# Rails.net
KiCad netlist of a schematic drawn in Altium Designer
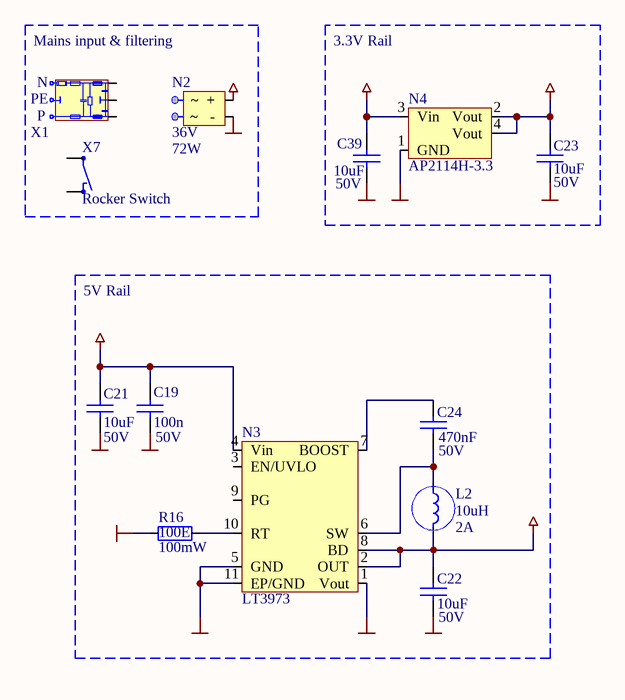
[diagram p0: Rails.SCHDOC]

(export (version "E")
  (design (tool "Eeschema 10.0.6"))
  (components
    (comp (ref "C19")
      (value "C_SMD_CER_100N_50V_10%_X7R_0603")
      (footprint "SMD_0603")
      (description "SMD Capacitor")
      (fields (field (name "ALTIUM_VALUE") "100n") (field (name "VALUE2") "50V"))
      (libsource (lib "C-Capacitor") (part "C_SMD_CER_100N_50V_10%_X7R_0603"))
    )
    (comp (ref "C21")
      (value "C_SMD_CER_10U_50V_10%_X7R_1210")
      (footprint "SMD_1210")
      (description "SMD Ceramic capacitor")
      (fields (field (name "ALTIUM_VALUE") "10uF") (field (name "VALUE2") "50V"))
      (libsource (lib "AM") (part "C_SMD_CER_10U_50V_10%_X7R_1210"))
    )
    (comp (ref "C22")
      (value "C_SMD_CER_10U_50V_10%_X7R_1210")
      (footprint "SMD_1210")
      (description "SMD Ceramic capacitor")
      (fields (field (name "ALTIUM_VALUE") "10uF") (field (name "VALUE2") "50V"))
      (libsource (lib "AM") (part "C_SMD_CER_10U_50V_10%_X7R_1210"))
    )
    (comp (ref "C23")
      (value "C_SMD_CER_10U_50V_10%_X7R_1210")
      (footprint "SMD_1210")
      (description "SMD Ceramic capacitor")
      (fields (field (name "ALTIUM_VALUE") "10uF") (field (name "VALUE2") "50V"))
      (libsource (lib "AM") (part "C_SMD_CER_10U_50V_10%_X7R_1210"))
    )
    (comp (ref "C24")
      (value "C_SMD_CER_470N_50V_10%_X7R_0603")
      (footprint "SMD_0603")
      (fields (field (name "ALTIUM_VALUE") "470nF") (field (name "VALUE2") "50V"))
      (libsource (lib "AM") (part "C_SMD_CER_470N_50V_10%_X7R_0603"))
    )
    (comp (ref "C39")
      (value "C_SMD_CER_10U_50V_10%_X7R_1210")
      (footprint "SMD_1210")
      (description "SMD Ceramic capacitor")
      (fields (field (name "ALTIUM_VALUE") "10uF") (field (name "VALUE2") "50V"))
      (libsource (lib "AM") (part "C_SMD_CER_10U_50V_10%_X7R_1210"))
    )
    (comp (ref "L2")
      (value "L_SMD_10U_2A_20%_IND_74477710")
      (footprint "SMD_INDUCT_74477710")
      (description "SMD Inductor")
      (fields (field (name "ALTIUM_VALUE") "10uH") (field (name "VALUE2") "2A"))
      (libsource (lib "AM") (part "L_SMD_10U_2A_20%_IND_74477710"))
    )
    (comp (ref "N2")
      (value "N_EXT_ACDC_36V_75W")
      (footprint "THT_CON_P2.54_D0.9_1X2")
      (fields (field (name "ALTIUM_VALUE") "36V") (field (name "VALUE2") "72W"))
      (libsource (lib "AM") (part "N_EXT_ACDC_36V_75W"))
    )
    (comp (ref "N3")
      (value "N_LT3973-5_DFN-10")
      (footprint "SMD_DFN_10_3X3")
      (description "42V, 750mA Step-Down Regulator with 2.5uA Quiescent Current and Integrated Diodes")
      (fields (field (name "TYPE") "LT3973"))
      (libsource (lib "N-Analog") (part "N_LT3973-5_DFN-10-3x3"))
    )
    (comp (ref "N4")
      (value "N_AP2114H-3.3_SOT223")
      (footprint "SMD_SOT_22_3")
      (description "1A Low Noise CMOS LDO Regulator")
      (fields (field (name "TYPE") "AP2114H-3.3"))
      (libsource (lib "N-Analog") (part "N_AP2114H-3.3_SOT223"))
    )
    (comp (ref "R16")
      (value "R_SMD_THINFILM_100E_0W1_1%_50PPM_0603")
      (footprint "SMD_0603")
      (description "SMD Resistor")
      (fields (field (name "ALTIUM_VALUE") "100E") (field (name "VALUE2") "100mW"))
      (libsource (lib "R-Resistor") (part "R_SMD_THINFILM_100E_0W1_1%_50PPM_0603"))
    )
    (comp (ref "X1")
      (value "X_POWER_ENTRY_MODULE_W/FILTER_W/FUSE_10A_SMD_CONNECTOR")
      (footprint "SMD_CON_P5.08_W2.0_L5.0_1X3")
      (description "MOD POWER ENTRY INLET WITH FUSE 10A")
      (libsource (lib "AM") (part "X_POWER_ENTRY_MODULE_W/FILTER_W/FUSE_10A_SMD_CONNECTOR"))
    )
    (comp (ref "X7")
      (value "X_SWITCH_ROCKER_SPST_6A_250VAC")
      (footprint "THT_CON_P5.08_D1.5_1X2")
      (fields (field (name "TYPE") "Rocker Switch"))
      (libsource (lib "X-Connectors") (part "X_SWITCH_ROCKER_SPST_6A_250VAC"))
    )
  )
  (nets
    (net (code "1") (name "+3.3V") (class "Default")
      (node (ref "C23") (pin "2") (pinfunction "2_2") (pintype "passive"))
      (node (ref "N4") (pin "2") (pinfunction "Vout_2") (pintype "passive"))
      (node (ref "N4") (pin "4") (pinfunction "Vout_4") (pintype "passive"))
    )
    (net (code "2") (name "+5V") (class "Default")
      (node (ref "C22") (pin "2") (pinfunction "2_2") (pintype "passive"))
      (node (ref "C39") (pin "2") (pinfunction "2_2") (pintype "passive"))
      (node (ref "L2") (pin "2") (pinfunction "2_2") (pintype "passive"))
      (node (ref "N3") (pin "2") (pinfunction "OUT_2") (pintype "passive"))
      (node (ref "N3") (pin "8") (pinfunction "BD_8") (pintype "passive"))
      (node (ref "N4") (pin "3") (pinfunction "Vin_3") (pintype "passive"))
    )
    (net (code "3") (name "+36V") (class "Default")
      (node (ref "C19") (pin "2") (pinfunction "2_2") (pintype "passive"))
      (node (ref "C21") (pin "2") (pinfunction "2_2") (pintype "passive"))
      (node (ref "N2") (pin "1") (pinfunction "~__+_1") (pintype "passive"))
      (node (ref "N3") (pin "4") (pinfunction "Vin_4") (pintype "passive"))
    )
    (net (code "4") (name "GND") (class "Default")
      (node (ref "C19") (pin "1") (pinfunction "1_1") (pintype "passive"))
      (node (ref "C21") (pin "1") (pinfunction "1_1") (pintype "passive"))
      (node (ref "C22") (pin "1") (pinfunction "1_1") (pintype "passive"))
      (node (ref "C23") (pin "1") (pinfunction "1_1") (pintype "passive"))
      (node (ref "C39") (pin "1") (pinfunction "1_1") (pintype "passive"))
      (node (ref "N2") (pin "2") (pinfunction "~___-_2") (pintype "passive"))
      (node (ref "N3") (pin "1") (pinfunction "Vout_1") (pintype "passive"))
      (node (ref "N3") (pin "11") (pinfunction "EP/GND_11") (pintype "passive"))
      (node (ref "N3") (pin "5") (pinfunction "GND_5") (pintype "passive"))
      (node (ref "N4") (pin "1") (pinfunction "GND_1") (pintype "passive"))
      (node (ref "R16") (pin "1") (pinfunction "1_1") (pintype "passive"))
    )
    (net (code "5") (name "Net-(N3-BOOST)") (class "Default")
      (node (ref "C24") (pin "2") (pinfunction "2_2") (pintype "passive"))
      (node (ref "N3") (pin "7") (pinfunction "BOOST_7") (pintype "passive"))
    )
    (net (code "6") (name "Net-(N3-RT)") (class "Default")
      (node (ref "N3") (pin "10") (pinfunction "RT_10") (pintype "passive"))
      (node (ref "R16") (pin "2") (pinfunction "2_2") (pintype "passive"))
    )
    (net (code "7") (name "Net-(N3-SW)") (class "Default")
      (node (ref "C24") (pin "1") (pinfunction "1_1") (pintype "passive"))
      (node (ref "L2") (pin "1") (pinfunction "1_1") (pintype "passive"))
      (node (ref "N3") (pin "6") (pinfunction "SW_6") (pintype "passive"))
    )
    (net (code "8") (name "unconnected-(N3-EN{slash}UVLO-Pad3)") (class "Default")
      (node (ref "N3") (pin "3") (pinfunction "EN/UVLO_3") (pintype "passive"))
    )
    (net (code "9") (name "unconnected-(N3-PG-Pad9)") (class "Default")
      (node (ref "N3") (pin "9") (pinfunction "PG_9") (pintype "passive"))
    )
    (net (code "10") (name "unconnected-(X1-Pad1)") (class "Default")
      (node (ref "X1") (pin "1") (pinfunction "1_1") (pintype "passive"))
    )
    (net (code "11") (name "unconnected-(X1-Pad2)") (class "Default")
      (node (ref "X1") (pin "2") (pinfunction "2_2") (pintype "passive"))
    )
    (net (code "12") (name "unconnected-(X1-Pad3)") (class "Default")
      (node (ref "X1") (pin "3") (pinfunction "3_3") (pintype "passive"))
    )
    (net (code "13") (name "unconnected-(X7-Pad1)") (class "Default")
      (node (ref "X7") (pin "1") (pinfunction "1_1") (pintype "passive"))
    )
    (net (code "14") (name "unconnected-(X7-Pad2)") (class "Default")
      (node (ref "X7") (pin "2") (pinfunction "2_2") (pintype "passive"))
    )
  )
)
